# TSOC_PSoC4L.net
KiCad netlist of a schematic drawn in EAGLE
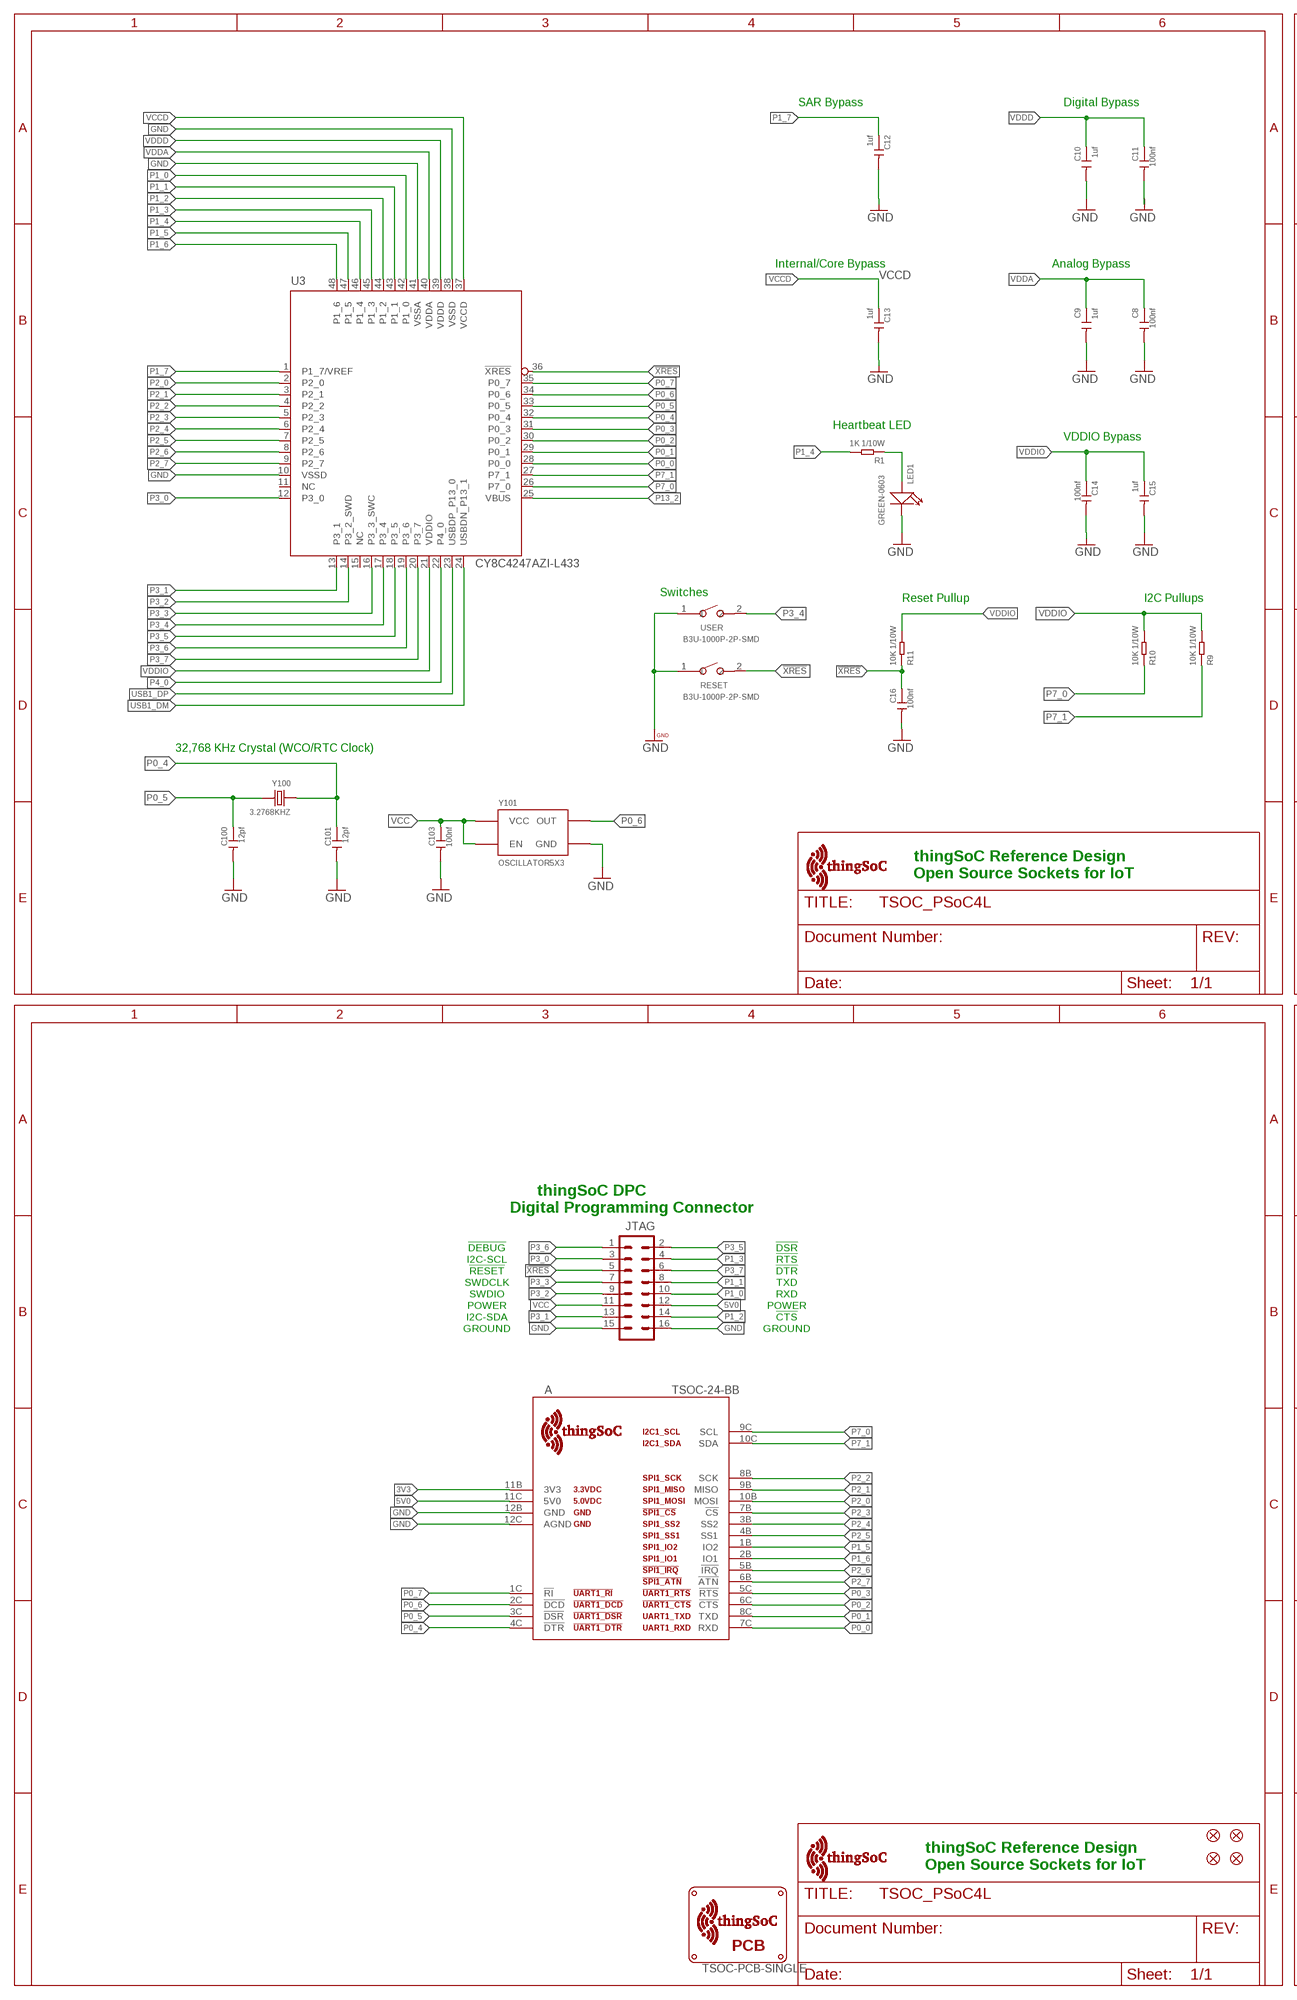
[diagram p0: schematic, sheet 1, part 1 of 2]
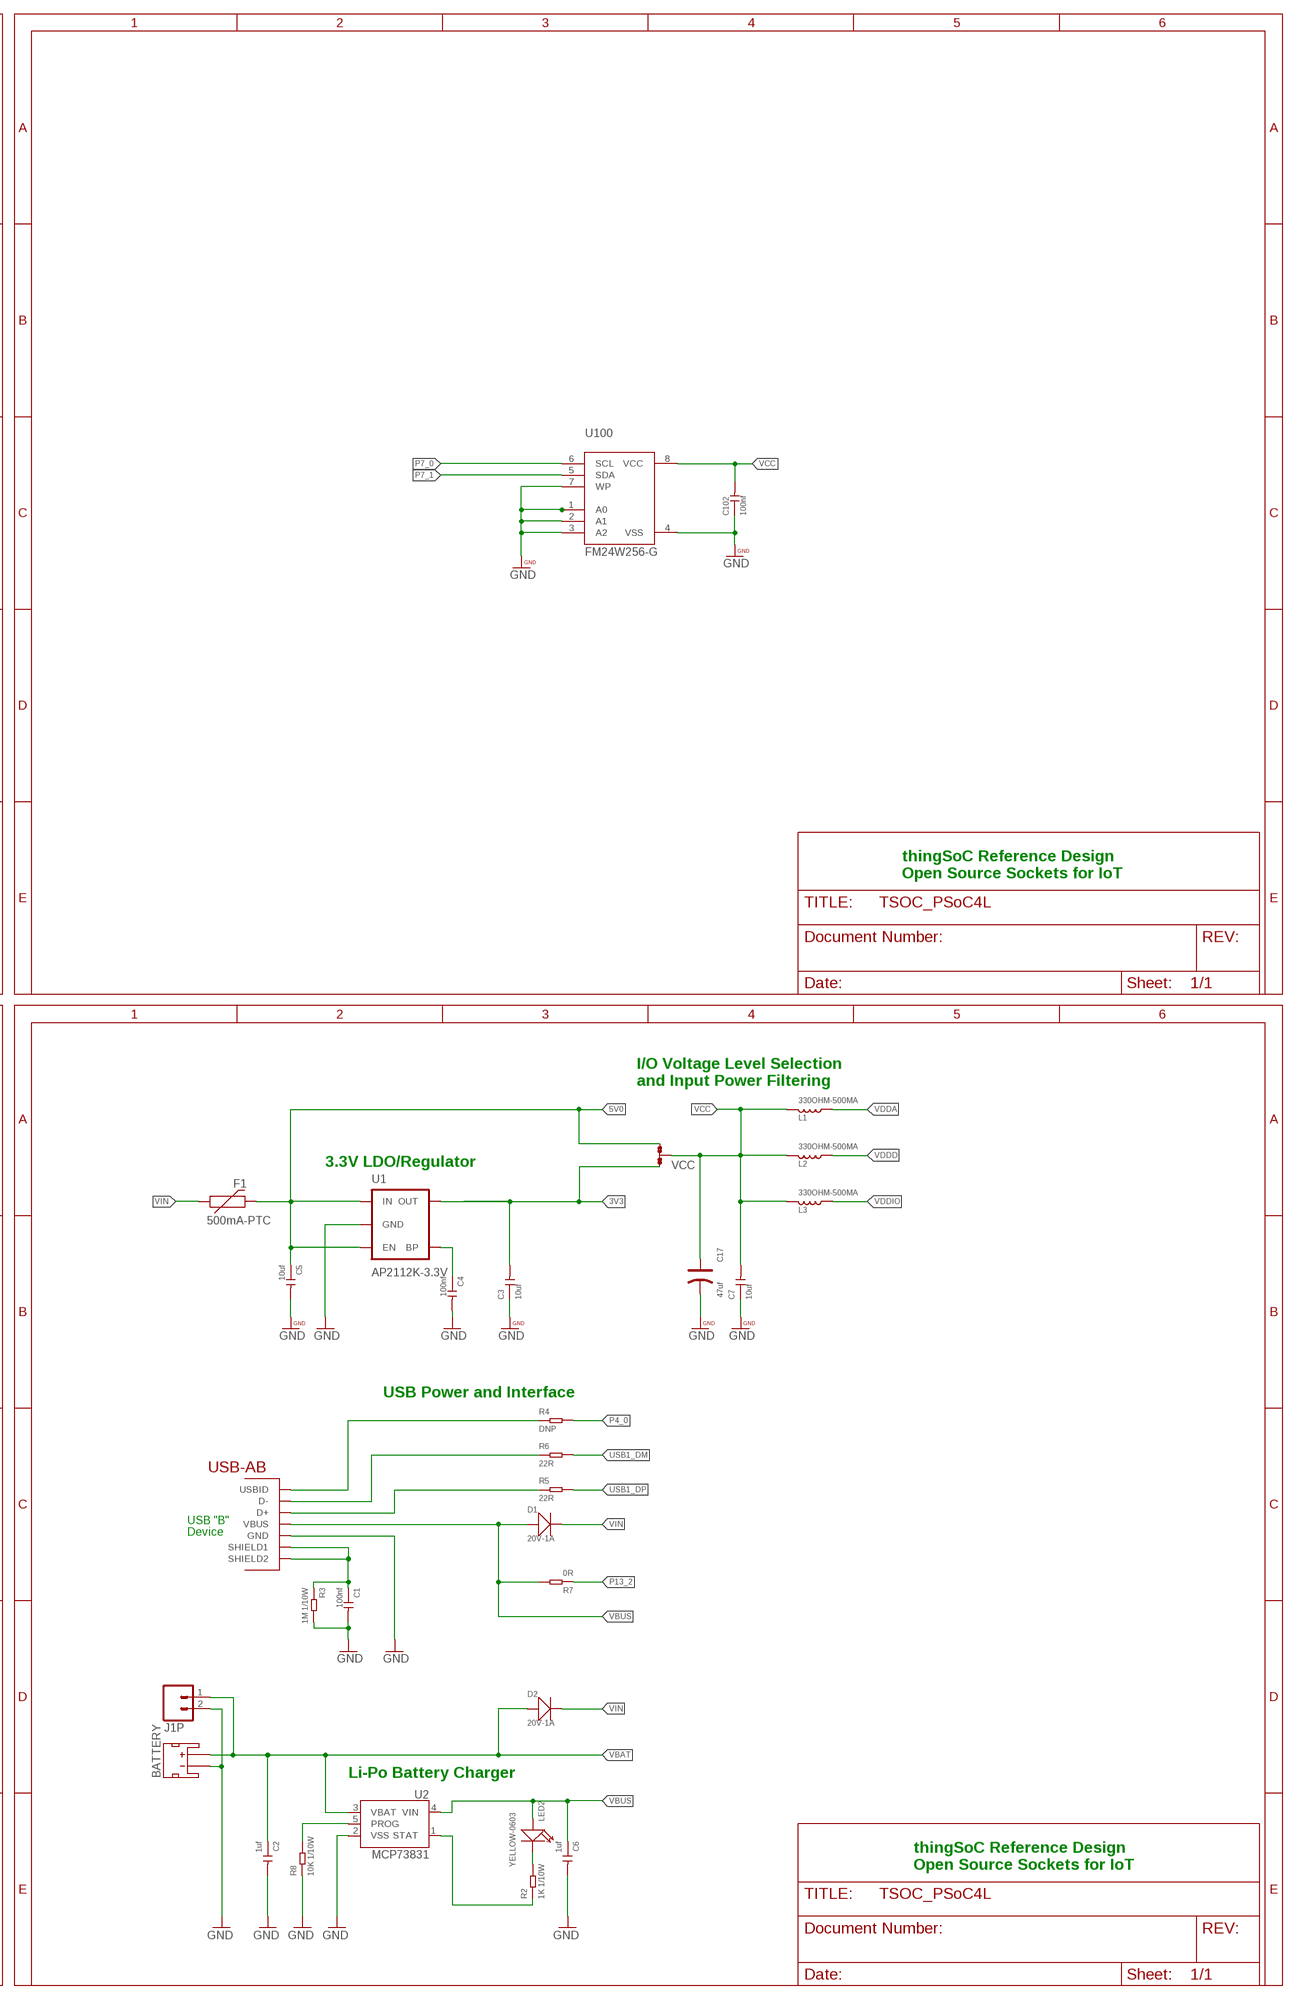
[diagram p1: schematic, sheet 1, part 2 of 2]

(export (version "E")
  (design (tool "Eeschema 10.0.6"))
  (components
    (comp (ref "A")
      (value "TSOC-24-BB")
      (footprint "eagle-import:TSOC-BB-S24")
      (libsource (lib "eagle-import") (part "TSOC-24-BB"))
    )
    (comp (ref "BATTERY")
      (value "JST_2MM_MALE")
      (footprint "eagle-import:JST-2-SMD")
      (libsource (lib "eagle-import") (part "JST_2MM_MALE"))
    )
    (comp (ref "C1")
      (value "100nf")
      (footprint "eagle-import:C0603")
      (fields (field (name "MPN") "CC0603KRX7R9BB104"))
      (libsource (lib "eagle-import") (part "CERAMIC-100NF-50V-10%-X7R(0603)"))
    )
    (comp (ref "C2")
      (value "1uf")
      (footprint "eagle-import:C0603")
      (fields (field (name "MPN") "CC0603KRX7R8BB105"))
      (libsource (lib "eagle-import") (part "CERAMIC-1UF-25V-10%-X7R(0603)"))
    )
    (comp (ref "C3")
      (value "10uf")
      (footprint "eagle-import:C0603")
      (fields (field (name "MPN") "CC0603KRX5R6BB106"))
      (libsource (lib "eagle-import") (part "CERAMIC-10UF-10V-10%-X5R(0603)"))
    )
    (comp (ref "C4")
      (value "100nf")
      (footprint "eagle-import:C0603")
      (fields (field (name "MPN") "CC0603KRX7R9BB104"))
      (libsource (lib "eagle-import") (part "CERAMIC-100NF-50V-10%-X7R(0603)"))
    )
    (comp (ref "C5")
      (value "10uf")
      (footprint "eagle-import:C0603")
      (fields (field (name "MPN") "CC0603KRX5R6BB106"))
      (libsource (lib "eagle-import") (part "CERAMIC-10UF-10V-10%-X5R(0603)"))
    )
    (comp (ref "C6")
      (value "1uf")
      (footprint "eagle-import:C0603")
      (fields (field (name "MPN") "CC0603KRX7R8BB105"))
      (libsource (lib "eagle-import") (part "CERAMIC-1UF-25V-10%-X7R(0603)"))
    )
    (comp (ref "C7")
      (value "10uf")
      (footprint "eagle-import:C0603")
      (fields (field (name "MPN") "CC0603KRX5R6BB106"))
      (libsource (lib "eagle-import") (part "CERAMIC-10UF-10V-10%-X5R(0603)"))
    )
    (comp (ref "C8")
      (value "100nf")
      (footprint "eagle-import:C0603")
      (fields (field (name "MPN") "CC0603KRX7R9BB104"))
      (libsource (lib "eagle-import") (part "CERAMIC-100NF-50V-10%-X7R(0603)"))
    )
    (comp (ref "C9")
      (value "1uf")
      (footprint "eagle-import:C0603")
      (fields (field (name "MPN") "CC0603KRX7R8BB105"))
      (libsource (lib "eagle-import") (part "CERAMIC-1UF-25V-10%-X7R(0603)"))
    )
    (comp (ref "C10")
      (value "1uf")
      (footprint "eagle-import:C0603")
      (fields (field (name "MPN") "CC0603KRX7R8BB105"))
      (libsource (lib "eagle-import") (part "CERAMIC-1UF-25V-10%-X7R(0603)"))
    )
    (comp (ref "C11")
      (value "100nf")
      (footprint "eagle-import:C0603")
      (fields (field (name "MPN") "CC0603KRX7R9BB104"))
      (libsource (lib "eagle-import") (part "CERAMIC-100NF-50V-10%-X7R(0603)"))
    )
    (comp (ref "C12")
      (value "1uf")
      (footprint "eagle-import:C0603")
      (fields (field (name "MPN") "CC0603KRX7R8BB105"))
      (libsource (lib "eagle-import") (part "CERAMIC-1UF-25V-10%-X7R(0603)"))
    )
    (comp (ref "C13")
      (value "1uf")
      (footprint "eagle-import:C0603")
      (fields (field (name "MPN") "CC0603KRX7R8BB105"))
      (libsource (lib "eagle-import") (part "CERAMIC-1UF-25V-10%-X7R(0603)"))
    )
    (comp (ref "C14")
      (value "100nf")
      (footprint "eagle-import:C0603")
      (fields (field (name "MPN") "CC0603KRX7R9BB104"))
      (libsource (lib "eagle-import") (part "CERAMIC-100NF-50V-10%-X7R(0603)"))
    )
    (comp (ref "C15")
      (value "1uf")
      (footprint "eagle-import:C0603")
      (fields (field (name "MPN") "CC0603KRX7R8BB105"))
      (libsource (lib "eagle-import") (part "CERAMIC-1UF-25V-10%-X7R(0603)"))
    )
    (comp (ref "C16")
      (value "100nf")
      (footprint "eagle-import:C0603")
      (fields (field (name "MPN") "CC0603KRX7R9BB104"))
      (libsource (lib "eagle-import") (part "CERAMIC-100NF-50V-10%-X7R(0603)"))
    )
    (comp (ref "C17")
      (value "47uf")
      (footprint "eagle-import:AVX-A")
      (fields (field (name "MPN") "TAJA476*006#NJ"))
      (libsource (lib "eagle-import") (part "TANTALUM-SMD-47UF-6.3V(AVX-A)"))
    )
    (comp (ref "C100")
      (value "12pf")
      (footprint "eagle-import:C0603")
      (fields (field (name "MPN") "CC0603JRNPO9BN120"))
      (libsource (lib "eagle-import") (part "CERAMIC-12PF-50V-5%-NPO(0603)"))
    )
    (comp (ref "C101")
      (value "12pf")
      (footprint "eagle-import:C0603")
      (fields (field (name "MPN") "CC0603JRNPO9BN120"))
      (libsource (lib "eagle-import") (part "CERAMIC-12PF-50V-5%-NPO(0603)"))
    )
    (comp (ref "C102")
      (value "100nf")
      (footprint "eagle-import:C0603")
      (fields (field (name "MPN") "CC0603KRX7R9BB104"))
      (libsource (lib "eagle-import") (part "CERAMIC-100NF-50V-10%-X7R(0603)"))
    )
    (comp (ref "C103")
      (value "100nf")
      (footprint "eagle-import:C0603")
      (fields (field (name "MPN") "CC0603KRX7R9BB104"))
      (libsource (lib "eagle-import") (part "CERAMIC-100NF-50V-10%-X7R(0603)"))
    )
    (comp (ref "D1")
      (value "20V-1A")
      (footprint "eagle-import:SOD-123")
      (fields (field (name "MPN") "B5819W"))
      (libsource (lib "eagle-import") (part "SMD-DIODE-SCHOTTKY-20V-1A(SOD-123)"))
    )
    (comp (ref "D2")
      (value "20V-1A")
      (footprint "eagle-import:SOD-123")
      (fields (field (name "MPN") "B5819W"))
      (libsource (lib "eagle-import") (part "SMD-DIODE-SCHOTTKY-20V-1A(SOD-123)"))
    )
    (comp (ref "F1")
      (value "500mA-PTC")
      (footprint "eagle-import:PTC-1206")
      (libsource (lib "eagle-import") (part "PTCSMD"))
    )
    (comp (ref "FID1")
      (value "FIDUCIALUFIDUCIAL")
      (footprint "eagle-import:MICRO-FIDUCIAL")
      (libsource (lib "eagle-import") (part "FIDUCIALUFIDUCIAL"))
    )
    (comp (ref "FID2")
      (value "FIDUCIALUFIDUCIAL")
      (footprint "eagle-import:MICRO-FIDUCIAL")
      (libsource (lib "eagle-import") (part "FIDUCIALUFIDUCIAL"))
    )
    (comp (ref "FID3")
      (value "FIDUCIALUFIDUCIAL")
      (footprint "eagle-import:MICRO-FIDUCIAL")
      (libsource (lib "eagle-import") (part "FIDUCIALUFIDUCIAL"))
    )
    (comp (ref "FID4")
      (value "FIDUCIALUFIDUCIAL")
      (footprint "eagle-import:MICRO-FIDUCIAL")
      (libsource (lib "eagle-import") (part "FIDUCIALUFIDUCIAL"))
    )
    (comp (ref "J1P")
      (value "M02-JST-2-PTH-NO_SILK")
      (footprint "eagle-import:JST-2-PTH-NS")
      (libsource (lib "eagle-import") (part "M02-JST-2-PTH-NO_SILK"))
    )
    (comp (ref "JTAG")
      (value "M08X2")
      (footprint "eagle-import:2X8")
      (libsource (lib "eagle-import") (part "M08X2"))
    )
    (comp (ref "L1")
      (value "330OHM-500MA")
      (footprint "eagle-import:L0603")
      (fields (field (name "MPN") "BLM18AG121SN1D"))
      (libsource (lib "eagle-import") (part "SMD-FERRITE-CHIP-120-OHM-500MA(0603)"))
    )
    (comp (ref "L2")
      (value "330OHM-500MA")
      (footprint "eagle-import:L0603")
      (fields (field (name "MPN") "BLM18AG121SN1D"))
      (libsource (lib "eagle-import") (part "SMD-FERRITE-CHIP-120-OHM-500MA(0603)"))
    )
    (comp (ref "L3")
      (value "330OHM-500MA")
      (footprint "eagle-import:L0603")
      (fields (field (name "MPN") "BLM18AG121SN1D"))
      (libsource (lib "eagle-import") (part "SMD-FERRITE-CHIP-120-OHM-500MA(0603)"))
    )
    (comp (ref "LED1")
      (value "GREEN-0603")
      (footprint "eagle-import:LED-0603")
      (fields (field (name "MPN") "19-217-G7C-AN1P2-3T"))
      (libsource (lib "eagle-import") (part "SMD-LED-CLEAR-GREEN(0603)"))
    )
    (comp (ref "LED2")
      (value "YELLOW-0603")
      (footprint "eagle-import:LED-0603")
      (fields (field (name "MPN") "19-217-Y5C-AM1N1VY-3T"))
      (libsource (lib "eagle-import") (part "SMD-LED-CLEAR-YELLOW(0603)"))
    )
    (comp (ref "R1")
      (value "1K 1/10W")
      (footprint "eagle-import:R0603")
      (fields (field (name "MPN") "RC0603JR-071KL"))
      (libsource (lib "eagle-import") (part "SMD-RES-1K-5%-1/10W(0603)"))
    )
    (comp (ref "R2")
      (value "1K 1/10W")
      (footprint "eagle-import:R0603")
      (fields (field (name "MPN") "RC0603JR-071KL"))
      (libsource (lib "eagle-import") (part "SMD-RES-1K-5%-1/10W(0603)"))
    )
    (comp (ref "R3")
      (value "1M 1/10W")
      (footprint "eagle-import:R0603")
      (fields (field (name "MPN") "RC0603JR-071ML"))
      (libsource (lib "eagle-import") (part "SMD-RES-1M-5%-1/10W(0603)"))
    )
    (comp (ref "R4")
      (value "DNP")
      (footprint "eagle-import:R0603")
      (fields (field (name "MPN") "RC0603JR-0722RL"))
      (libsource (lib "eagle-import") (part "SMD-RES-22R-5%-1/10W(0603)"))
    )
    (comp (ref "R5")
      (value "22R")
      (footprint "eagle-import:R0603")
      (fields (field (name "MPN") "RC0603JR-0722RL"))
      (libsource (lib "eagle-import") (part "SMD-RES-22R-5%-1/10W(0603)"))
    )
    (comp (ref "R6")
      (value "22R")
      (footprint "eagle-import:R0603")
      (fields (field (name "MPN") "RC0603JR-0722RL"))
      (libsource (lib "eagle-import") (part "SMD-RES-22R-5%-1/10W(0603)"))
    )
    (comp (ref "R7")
      (value "0R")
      (footprint "eagle-import:R0603")
      (fields (field (name "MPN") "RC0603JR-070RL"))
      (libsource (lib "eagle-import") (part "SMD-RES-0R-5%-1/10W(0603)"))
    )
    (comp (ref "R8")
      (value "10K 1/10W")
      (footprint "eagle-import:R0603")
      (fields (field (name "MPN") "RC0603JR-0710KL"))
      (libsource (lib "eagle-import") (part "SMD-RES-10K-5%-1/10W(0603)"))
    )
    (comp (ref "R9")
      (value "10K 1/10W")
      (footprint "eagle-import:R0603")
      (fields (field (name "MPN") "RC0603JR-0710KL"))
      (libsource (lib "eagle-import") (part "SMD-RES-10K-5%-1/10W(0603)"))
    )
    (comp (ref "R10")
      (value "10K 1/10W")
      (footprint "eagle-import:R0603")
      (fields (field (name "MPN") "RC0603JR-0710KL"))
      (libsource (lib "eagle-import") (part "SMD-RES-10K-5%-1/10W(0603)"))
    )
    (comp (ref "R11")
      (value "10K 1/10W")
      (footprint "eagle-import:R0603")
      (fields (field (name "MPN") "RC0603JR-0710KL"))
      (libsource (lib "eagle-import") (part "SMD-RES-10K-5%-1/10W(0603)"))
    )
    (comp (ref "RESET")
      (value "B3U-1000P-2P-SMD")
      (footprint "eagle-import:SW2-2.6-3.0X2.5X1.2+0.4MM")
      (libsource (lib "eagle-import") (part "SMD-BUTTON(2P-3.0X2.5X1.2+0.4MM)-B3U-1000P-2P-SMD"))
    )
    (comp (ref "U$1")
      (value "TSOC-PCB-SINGLE")
      (footprint "eagle-import:TSOC-BB-BRD-DIM")
      (libsource (lib "eagle-import") (part "TSOC-PCB-SINGLE"))
    )
    (comp (ref "U$100")
      (value "TSOC-LOGO-LRG")
      (footprint "eagle-import:TSOC-LOGO-LRG")
      (libsource (lib "eagle-import") (part "TSOC-LOGO-LRG"))
    )
    (comp (ref "U$101")
      (value "TSOC-LOGO-SMALL")
      (footprint "eagle-import:TSOC-LOGO-SML")
      (libsource (lib "eagle-import") (part "TSOC-LOGO-SMALL"))
    )
    (comp (ref "U1")
      (value "AP2112K-3.3V")
      (footprint "eagle-import:SOT23-5")
      (libsource (lib "eagle-import") (part "V_REG_LDOSMD"))
    )
    (comp (ref "U2")
      (value "MCP73831")
      (footprint "eagle-import:SOT23-5")
      (libsource (lib "eagle-import") (part "MCP73831"))
    )
    (comp (ref "U3")
      (value "CY8C4247AZI-L433")
      (footprint "eagle-import:TQFP-7X7-48")
      (libsource (lib "eagle-import") (part "CY8C4247AZI-L433"))
    )
    (comp (ref "U100")
      (value "FM24W256-G")
      (footprint "eagle-import:SO08")
      (libsource (lib "eagle-import") (part "FM24W256-G"))
    )
    (comp (ref "USB")
      (value "USB_AB")
      (footprint "eagle-import:USB-AB-MICRO-SMD")
      (libsource (lib "eagle-import") (part "USB_AB"))
    )
    (comp (ref "USER")
      (value "B3U-1000P-2P-SMD")
      (footprint "eagle-import:SW2-2.6-3.0X2.5X1.2+0.4MM")
      (libsource (lib "eagle-import") (part "SMD-BUTTON(2P-3.0X2.5X1.2+0.4MM)-B3U-1000P-2P-SMD"))
    )
    (comp (ref "VCC")
      (value "JMP-3-1_2")
      (footprint "eagle-import:JMP-3-1_2")
      (libsource (lib "eagle-import") (part "JMP-3-1_2"))
    )
    (comp (ref "Y100")
      (value "3.2768KHZ")
      (footprint "eagle-import:X2-SMD-L2.0X1.2X0.55MM")
      (fields (field (name "MPN") "FC-12M"))
      (libsource (lib "eagle-import") (part "SMD-CRYSTAL-32.768KHZ-12.5PF-20PPM-90K(2P-L2.0X1.2MM)"))
    )
    (comp (ref "Y101")
      (value "OSCILLATOR5X3")
      (footprint "eagle-import:CRYSTAL-SMD-5X3")
      (libsource (lib "eagle-import") (part "OSCILLATOR5X3"))
    )
  )
  (nets
    (net (code "1") (name "/~{XRES}") (class "Default")
      (node (ref "C16") (pin "1") (pinfunction "1_1") (pintype "passive"))
      (node (ref "JTAG") (pin "5") (pinfunction "5_5") (pintype "passive"))
      (node (ref "R11") (pin "1") (pinfunction "1_1") (pintype "passive"))
      (node (ref "RESET") (pin "2") (pinfunction "2_2") (pintype "bidirectional"))
      (node (ref "U3") (pin "36") (pinfunction "~{XRES}_36") (pintype "bidirectional"))
    )
    (net (code "2") (name "3V3") (class "Default")
      (node (ref "A") (pin "11B") (pinfunction "3V3_11B") (pintype "bidirectional"))
      (node (ref "C3") (pin "2") (pinfunction "2_2") (pintype "passive"))
      (node (ref "U1") (pin "5") (pinfunction "OUT_5") (pintype "passive"))
      (node (ref "VCC") (pin "1") (pinfunction "1_1") (pintype "passive"))
    )
    (net (code "3") (name "5V0") (class "Default")
      (node (ref "A") (pin "11C") (pinfunction "5V0_11C") (pintype "bidirectional"))
      (node (ref "C5") (pin "1") (pinfunction "1_1") (pintype "passive"))
      (node (ref "F1") (pin "2") (pinfunction "2_2") (pintype "bidirectional"))
      (node (ref "JTAG") (pin "12") (pinfunction "12_12") (pintype "passive"))
      (node (ref "U1") (pin "1") (pinfunction "IN_1") (pintype "input"))
      (node (ref "U1") (pin "3") (pinfunction "EN_3") (pintype "input"))
      (node (ref "VCC") (pin "3") (pinfunction "3_3") (pintype "passive"))
    )
    (net (code "4") (name "GND") (class "Default")
      (node (ref "A") (pin "12B") (pinfunction "GND_12B") (pintype "bidirectional"))
      (node (ref "A") (pin "12C") (pinfunction "AGND_12C") (pintype "bidirectional"))
      (node (ref "BATTERY") (pin "1") (pinfunction "-_1") (pintype "bidirectional"))
      (node (ref "C1") (pin "2") (pinfunction "2_2") (pintype "passive"))
      (node (ref "C10") (pin "2") (pinfunction "2_2") (pintype "passive"))
      (node (ref "C100") (pin "2") (pinfunction "2_2") (pintype "passive"))
      (node (ref "C101") (pin "2") (pinfunction "2_2") (pintype "passive"))
      (node (ref "C102") (pin "1") (pinfunction "1_1") (pintype "passive"))
      (node (ref "C103") (pin "2") (pinfunction "2_2") (pintype "passive"))
      (node (ref "C11") (pin "2") (pinfunction "2_2") (pintype "passive"))
      (node (ref "C12") (pin "2") (pinfunction "2_2") (pintype "passive"))
      (node (ref "C13") (pin "2") (pinfunction "2_2") (pintype "passive"))
      (node (ref "C14") (pin "2") (pinfunction "2_2") (pintype "passive"))
      (node (ref "C15") (pin "2") (pinfunction "2_2") (pintype "passive"))
      (node (ref "C16") (pin "2") (pinfunction "2_2") (pintype "passive"))
      (node (ref "C17") (pin "-") (pinfunction "-_-") (pintype "passive"))
      (node (ref "C2") (pin "2") (pinfunction "2_2") (pintype "passive"))
      (node (ref "C3") (pin "1") (pinfunction "1_1") (pintype "passive"))
      (node (ref "C4") (pin "2") (pinfunction "2_2") (pintype "passive"))
      (node (ref "C5") (pin "2") (pinfunction "2_2") (pintype "passive"))
      (node (ref "C6") (pin "2") (pinfunction "2_2") (pintype "passive"))
      (node (ref "C7") (pin "1") (pinfunction "1_1") (pintype "passive"))
      (node (ref "C8") (pin "2") (pinfunction "2_2") (pintype "passive"))
      (node (ref "C9") (pin "2") (pinfunction "2_2") (pintype "passive"))
      (node (ref "J1P") (pin "2") (pinfunction "2_2") (pintype "passive"))
      (node (ref "JTAG") (pin "15") (pinfunction "15_15") (pintype "passive"))
      (node (ref "JTAG") (pin "16") (pinfunction "16_16") (pintype "passive"))
      (node (ref "LED1") (pin "-") (pinfunction "-_-") (pintype "passive"))
      (node (ref "R3") (pin "2") (pinfunction "2_2") (pintype "passive"))
      (node (ref "R8") (pin "1") (pinfunction "1_1") (pintype "passive"))
      (node (ref "RESET") (pin "1") (pinfunction "1_1") (pintype "bidirectional"))
      (node (ref "U1") (pin "2") (pinfunction "GND_2") (pintype "input"))
      (node (ref "U100") (pin "1") (pinfunction "A0_1") (pintype "bidirectional"))
      (node (ref "U100") (pin "2") (pinfunction "A1_2") (pintype "bidirectional"))
      (node (ref "U100") (pin "3") (pinfunction "A2_3") (pintype "bidirectional"))
      (node (ref "U100") (pin "4") (pinfunction "VSS_4") (pintype "power_in"))
      (node (ref "U100") (pin "7") (pinfunction "WP_7") (pintype "bidirectional"))
      (node (ref "U2") (pin "2") (pinfunction "VSS_2") (pintype "power_in"))
      (node (ref "U3") (pin "10") (pinfunction "VSSD_10") (pintype "bidirectional"))
      (node (ref "U3") (pin "38") (pinfunction "VSSD_38") (pintype "bidirectional"))
      (node (ref "U3") (pin "41") (pinfunction "VSSA_41") (pintype "bidirectional"))
      (node (ref "USB") (pin "GND") (pinfunction "GND_GND") (pintype "bidirectional"))
      (node (ref "USER") (pin "1") (pinfunction "1_1") (pintype "bidirectional"))
      (node (ref "Y101") (pin "2") (pinfunction "GND_2") (pintype "bidirectional"))
    )
    (net (code "5") (name "Net-(C1-Pad1)") (class "Default")
      (node (ref "C1") (pin "1") (pinfunction "1_1") (pintype "passive"))
      (node (ref "R3") (pin "1") (pinfunction "1_1") (pintype "passive"))
      (node (ref "USB") (pin "SHIELD1") (pinfunction "SHIELD1_SHIELD1") (pintype "bidirectional"))
      (node (ref "USB") (pin "SHIELD2") (pinfunction "SHIELD2_SHIELD2") (pintype "bidirectional"))
    )
    (net (code "6") (name "Net-(LED1-Pad+)") (class "Default")
      (node (ref "LED1") (pin "+") (pinfunction "+_+") (pintype "passive"))
      (node (ref "R1") (pin "1") (pinfunction "1_1") (pintype "passive"))
    )
    (net (code "7") (name "Net-(LED2-Pad-)") (class "Default")
      (node (ref "LED2") (pin "-") (pinfunction "-_-") (pintype "passive"))
      (node (ref "R2") (pin "2") (pinfunction "2_2") (pintype "passive"))
    )
    (net (code "8") (name "Net-(R5-Pad1)") (class "Default")
      (node (ref "R5") (pin "1") (pinfunction "1_1") (pintype "passive"))
      (node (ref "USB") (pin "D+") (pinfunction "D+_D+") (pintype "bidirectional"))
    )
    (net (code "9") (name "Net-(R6-Pad1)") (class "Default")
      (node (ref "R6") (pin "1") (pinfunction "1_1") (pintype "passive"))
      (node (ref "USB") (pin "D-") (pinfunction "D-_D-") (pintype "bidirectional"))
    )
    (net (code "10") (name "Net-(U1-BP)") (class "Default")
      (node (ref "C4") (pin "1") (pinfunction "1_1") (pintype "passive"))
      (node (ref "U1") (pin "4") (pinfunction "BP_4") (pintype "input"))
    )
    (net (code "11") (name "Net-(U2-PROG)") (class "Default")
      (node (ref "R8") (pin "2") (pinfunction "2_2") (pintype "passive"))
      (node (ref "U2") (pin "5") (pinfunction "PROG_5") (pintype "input"))
    )
    (net (code "12") (name "Net-(U2-STAT)") (class "Default")
      (node (ref "R2") (pin "1") (pinfunction "1_1") (pintype "passive"))
      (node (ref "U2") (pin "1") (pinfunction "STAT_1") (pintype "output"))
    )
    (net (code "13") (name "Net-(USB-USBID)") (class "Default")
      (node (ref "R4") (pin "1") (pinfunction "1_1") (pintype "passive"))
      (node (ref "USB") (pin "ID") (pinfunction "USBID_ID") (pintype "bidirectional"))
    )
    (net (code "14") (name "P0_0") (class "Default")
      (node (ref "A") (pin "7C") (pinfunction "RXD_7C") (pintype "bidirectional"))
      (node (ref "U3") (pin "28") (pinfunction "P0_0_28") (pintype "bidirectional"))
    )
    (net (code "15") (name "P0_1") (class "Default")
      (node (ref "A") (pin "8C") (pinfunction "TXD_8C") (pintype "bidirectional"))
      (node (ref "U3") (pin "29") (pinfunction "P0_1_29") (pintype "bidirectional"))
    )
    (net (code "16") (name "P0_2") (class "Default")
      (node (ref "A") (pin "6C") (pinfunction "~{CTS}_6C") (pintype "bidirectional"))
      (node (ref "U3") (pin "30") (pinfunction "P0_2_30") (pintype "input"))
    )
    (net (code "17") (name "P0_3") (class "Default")
      (node (ref "A") (pin "5C") (pinfunction "~{RTS}_5C") (pintype "bidirectional"))
      (node (ref "U3") (pin "31") (pinfunction "P0_3_31") (pintype "bidirectional"))
    )
    (net (code "18") (name "P0_4") (class "Default")
      (node (ref "A") (pin "4C") (pinfunction "~{DTR}_4C") (pintype "bidirectional"))
      (node (ref "C101") (pin "1") (pinfunction "1_1") (pintype "passive"))
      (node (ref "U3") (pin "32") (pinfunction "P0_4_32") (pintype "bidirectional"))
      (node (ref "Y100") (pin "1") (pinfunction "1_1") (pintype "passive"))
    )
    (net (code "19") (name "P0_5") (class "Default")
      (node (ref "A") (pin "3C") (pinfunction "~{DSR}_3C") (pintype "bidirectional"))
      (node (ref "C100") (pin "1") (pinfunction "1_1") (pintype "passive"))
      (node (ref "U3") (pin "33") (pinfunction "P0_5_33") (pintype "bidirectional"))
      (node (ref "Y100") (pin "2") (pinfunction "2_2") (pintype "passive"))
    )
    (net (code "20") (name "P0_6") (class "Default")
      (node (ref "A") (pin "2C") (pinfunction "~{DCD}_2C") (pintype "bidirectional"))
      (node (ref "U3") (pin "34") (pinfunction "P0_6_34") (pintype "power_in"))
      (node (ref "Y101") (pin "3") (pinfunction "OUT_3") (pintype "bidirectional"))
    )
    (net (code "21") (name "P0_7") (class "Default")
      (node (ref "A") (pin "1C") (pinfunction "~{RI}_1C") (pintype "bidirectional"))
      (node (ref "U3") (pin "35") (pinfunction "P0_7_35") (pintype "bidirectional"))
    )
    (net (code "22") (name "P1_0") (class "Default")
      (node (ref "JTAG") (pin "10") (pinfunction "10_10") (pintype "passive"))
      (node (ref "U3") (pin "42") (pinfunction "P1_0_42") (pintype "bidirectional"))
    )
    (net (code "23") (name "P1_1") (class "Default")
      (node (ref "JTAG") (pin "8") (pinfunction "8_8") (pintype "passive"))
      (node (ref "U3") (pin "43") (pinfunction "P1_1_43") (pintype "bidirectional"))
    )
    (net (code "24") (name "P1_2") (class "Default")
      (node (ref "JTAG") (pin "14") (pinfunction "14_14") (pintype "passive"))
      (node (ref "U3") (pin "44") (pinfunction "P1_2_44") (pintype "power_in"))
    )
    (net (code "25") (name "P1_3") (class "Default")
      (node (ref "JTAG") (pin "4") (pinfunction "4_4") (pintype "passive"))
      (node (ref "U3") (pin "45") (pinfunction "P1_3_45") (pintype "bidirectional"))
    )
    (net (code "26") (name "P1_4") (class "Default")
      (node (ref "R1") (pin "2") (pinfunction "2_2") (pintype "passive"))
      (node (ref "U3") (pin "46") (pinfunction "P1_4_46") (pintype "bidirectional"))
    )
    (net (code "27") (name "P1_5") (class "Default")
      (node (ref "A") (pin "1B") (pinfunction "IO2_1B") (pintype "bidirectional"))
      (node (ref "U3") (pin "47") (pinfunction "P1_5_47") (pintype "bidirectional"))
    )
    (net (code "28") (name "P1_6") (class "Default")
      (node (ref "A") (pin "2B") (pinfunction "IO1_2B") (pintype "bidirectional"))
      (node (ref "U3") (pin "48") (pinfunction "P1_6_48") (pintype "bidirectional"))
    )
    (net (code "29") (name "P1_7") (class "Default")
      (node (ref "C12") (pin "1") (pinfunction "1_1") (pintype "passive"))
      (node (ref "U3") (pin "1") (pinfunction "P1_7/VREF_1") (pintype "bidirectional"))
    )
    (net (code "30") (name "P2_0") (class "Default")
      (node (ref "A") (pin "10B") (pinfunction "MOSI_10B") (pintype "bidirectional"))
      (node (ref "U3") (pin "2") (pinfunction "P2_0_2") (pintype "bidirectional"))
    )
    (net (code "31") (name "P2_1") (class "Default")
      (node (ref "A") (pin "9B") (pinfunction "MISO_9B") (pintype "bidirectional"))
      (node (ref "U3") (pin "3") (pinfunction "P2_1_3") (pintype "bidirectional"))
    )
    (net (code "32") (name "P2_2") (class "Default")
      (node (ref "A") (pin "8B") (pinfunction "SCK_8B") (pintype "bidirectional"))
      (node (ref "U3") (pin "4") (pinfunction "P2_2_4") (pintype "power_in"))
    )
    (net (code "33") (name "P2_3") (class "Default")
      (node (ref "A") (pin "7B") (pinfunction "~{CS}_7B") (pintype "bidirectional"))
      (node (ref "U3") (pin "5") (pinfunction "P2_3_5") (pintype "bidirectional"))
    )
    (net (code "34") (name "P2_4") (class "Default")
      (node (ref "A") (pin "3B") (pinfunction "SS2_3B") (pintype "bidirectional"))
      (node (ref "U3") (pin "6") (pinfunction "P2_4_6") (pintype "bidirectional"))
    )
    (net (code "35") (name "P2_5") (class "Default")
      (node (ref "A") (pin "4B") (pinfunction "SS1_4B") (pintype "bidirectional"))
      (node (ref "U3") (pin "7") (pinfunction "P2_5_7") (pintype "bidirectional"))
    )
    (net (code "36") (name "P2_6") (class "Default")
      (node (ref "A") (pin "5B") (pinfunction "~{IRQ}_5B") (pintype "bidirectional"))
      (node (ref "U3") (pin "8") (pinfunction "P2_6_8") (pintype "power_in"))
    )
    (net (code "37") (name "P2_7") (class "Default")
      (node (ref "A") (pin "6B") (pinfunction "~{ATN}_6B") (pintype "bidirectional"))
      (node (ref "U3") (pin "9") (pinfunction "P2_7_9") (pintype "bidirectional"))
    )
    (net (code "38") (name "P3_0") (class "Default")
      (node (ref "JTAG") (pin "3") (pinfunction "3_3") (pintype "passive"))
      (node (ref "U3") (pin "12") (pinfunction "P3_0_12") (pintype "bidirectional"))
    )
    (net (code "39") (name "P3_1") (class "Default")
      (node (ref "JTAG") (pin "13") (pinfunction "13_13") (pintype "passive"))
      (node (ref "U3") (pin "13") (pinfunction "P3_1_13") (pintype "bidirectional"))
    )
    (net (code "40") (name "P3_2") (class "Default")
      (node (ref "JTAG") (pin "9") (pinfunction "9_9") (pintype "passive"))
      (node (ref "U3") (pin "14") (pinfunction "P3_2_SWD_14") (pintype "bidirectional"))
    )
    (net (code "41") (name "P3_3") (class "Default")
      (node (ref "JTAG") (pin "7") (pinfunction "7_7") (pintype "passive"))
      (node (ref "U3") (pin "16") (pinfunction "P3_3_SWC_16") (pintype "bidirectional"))
    )
    (net (code "42") (name "P3_4") (class "Default")
      (node (ref "U3") (pin "17") (pinfunction "P3_4_17") (pintype "bidirectional"))
      (node (ref "USER") (pin "2") (pinfunction "2_2") (pintype "bidirectional"))
    )
    (net (code "43") (name "P3_5") (class "Default")
      (node (ref "JTAG") (pin "2") (pinfunction "2_2") (pintype "passive"))
      (node (ref "U3") (pin "18") (pinfunction "P3_5_18") (pintype "bidirectional"))
    )
    (net (code "44") (name "P3_6") (class "Default")
      (node (ref "JTAG") (pin "1") (pinfunction "1_1") (pintype "passive"))
      (node (ref "U3") (pin "19") (pinfunction "P3_6_19") (pintype "power_in"))
    )
    (net (code "45") (name "P3_7") (class "Default")
      (node (ref "JTAG") (pin "6") (pinfunction "6_6") (pintype "passive"))
      (node (ref "U3") (pin "20") (pinfunction "P3_7_20") (pintype "bidirectional"))
    )
    (net (code "46") (name "P4_0") (class "Default")
      (node (ref "R4") (pin "2") (pinfunction "2_2") (pintype "passive"))
      (node (ref "U3") (pin "22") (pinfunction "P4_0_22") (pintype "bidirectional"))
    )
    (net (code "47") (name "P7_0") (class "Default")
      (node (ref "A") (pin "9C") (pinfunction "SCL_9C") (pintype "bidirectional"))
      (node (ref "R10") (pin "1") (pinfunction "1_1") (pintype "passive"))
      (node (ref "U100") (pin "6") (pinfunction "SCL_6") (pintype "bidirectional"))
      (node (ref "U3") (pin "26") (pinfunction "P7_0_26") (pintype "bidirectional"))
    )
    (net (code "48") (name "P7_1") (class "Default")
      (node (ref "A") (pin "10C") (pinfunction "SDA_10C") (pintype "bidirectional"))
      (node (ref "R9") (pin "1") (pinfunction "1_1") (pintype "passive"))
      (node (ref "U100") (pin "5") (pinfunction "SDA_5") (pintype "bidirectional"))
      (node (ref "U3") (pin "27") (pinfunction "P7_1_27") (pintype "bidirectional"))
    )
    (net (code "49") (name "P13_2") (class "Default")
      (node (ref "R7") (pin "1") (pinfunction "1_1") (pintype "passive"))
      (node (ref "U3") (pin "25") (pinfunction "VBUS_25") (pintype "bidirectional"))
    )
    (net (code "50") (name "USB1_DM") (class "Default")
      (node (ref "R6") (pin "2") (pinfunction "2_2") (pintype "passive"))
      (node (ref "U3") (pin "24") (pinfunction "USBDN_P13_1_24") (pintype "bidirectional"))
    )
    (net (code "51") (name "USB1_DP") (class "Default")
      (node (ref "R5") (pin "2") (pinfunction "2_2") (pintype "passive"))
      (node (ref "U3") (pin "23") (pinfunction "USBDP_P13_0_23") (pintype "bidirectional"))
    )
    (net (code "52") (name "VBAT") (class "Default")
      (node (ref "BATTERY") (pin "2") (pinfunction "+_2") (pintype "bidirectional"))
      (node (ref "C2") (pin "1") (pinfunction "1_1") (pintype "passive"))
      (node (ref "D2") (pin "+") (pinfunction "+_+") (pintype "passive"))
      (node (ref "J1P") (pin "1") (pinfunction "1_1") (pintype "passive"))
      (node (ref "U2") (pin "3") (pinfunction "VBAT_3") (pintype "power_in"))
    )
    (net (code "53") (name "VBUS") (class "Default")
      (node (ref "C6") (pin "1") (pinfunction "1_1") (pintype "passive"))
      (node (ref "D1") (pin "+") (pinfunction "+_+") (pintype "passive"))
      (node (ref "LED2") (pin "+") (pinfunction "+_+") (pintype "passive"))
      (node (ref "R7") (pin "2") (pinfunction "2_2") (pintype "passive"))
      (node (ref "U2") (pin "4") (pinfunction "VIN_4") (pintype "power_in"))
      (node (ref "USB") (pin "VBUS") (pinfunction "VBUS_VBUS") (pintype "bidirectional"))
    )
    (net (code "54") (name "VCC") (class "Default")
      (node (ref "C102") (pin "2") (pinfunction "2_2") (pintype "passive"))
      (node (ref "C103") (pin "1") (pinfunction "1_1") (pintype "passive"))
      (node (ref "C17") (pin "+") (pinfunction "+_+") (pintype "passive"))
      (node (ref "C7") (pin "2") (pinfunction "2_2") (pintype "passive"))
      (node (ref "JTAG") (pin "11") (pinfunction "11_11") (pintype "passive"))
      (node (ref "L1") (pin "1") (pinfunction "1_1") (pintype "passive"))
      (node (ref "L2") (pin "1") (pinfunction "1_1") (pintype "passive"))
      (node (ref "L3") (pin "1") (pinfunction "1_1") (pintype "passive"))
      (node (ref "U100") (pin "8") (pinfunction "VCC_8") (pintype "power_in"))
      (node (ref "VCC") (pin "2") (pinfunction "2_2") (pintype "passive"))
      (node (ref "Y101") (pin "1") (pinfunction "EN_1") (pintype "bidirectional"))
      (node (ref "Y101") (pin "4") (pinfunction "VCC_4") (pintype "bidirectional"))
    )
    (net (code "55") (name "VCCD") (class "Default")
      (node (ref "C13") (pin "1") (pinfunction "1_1") (pintype "passive"))
      (node (ref "U3") (pin "37") (pinfunction "VCCD_37") (pintype "bidirectional"))
    )
    (net (code "56") (name "VDDA") (class "Default")
      (node (ref "C8") (pin "1") (pinfunction "1_1") (pintype "passive"))
      (node (ref "C9") (pin "1") (pinfunction "1_1") (pintype "passive"))
      (node (ref "L1") (pin "2") (pinfunction "2_2") (pintype "passive"))
      (node (ref "U3") (pin "40") (pinfunction "VDDA_40") (pintype "bidirectional"))
    )
    (net (code "57") (name "VDDD") (class "Default")
      (node (ref "C10") (pin "1") (pinfunction "1_1") (pintype "passive"))
      (node (ref "C11") (pin "1") (pinfunction "1_1") (pintype "passive"))
      (node (ref "L2") (pin "2") (pinfunction "2_2") (pintype "passive"))
      (node (ref "U3") (pin "39") (pinfunction "VDDD_39") (pintype "bidirectional"))
    )
    (net (code "58") (name "VDDIO") (class "Default")
      (node (ref "C14") (pin "1") (pinfunction "1_1") (pintype "passive"))
      (node (ref "C15") (pin "1") (pinfunction "1_1") (pintype "passive"))
      (node (ref "L3") (pin "2") (pinfunction "2_2") (pintype "passive"))
      (node (ref "R10") (pin "2") (pinfunction "2_2") (pintype "passive"))
      (node (ref "R11") (pin "2") (pinfunction "2_2") (pintype "passive"))
      (node (ref "R9") (pin "2") (pinfunction "2_2") (pintype "passive"))
      (node (ref "U3") (pin "21") (pinfunction "VDDIO_21") (pintype "bidirectional"))
    )
    (net (code "59") (name "VIN") (class "Default")
      (node (ref "D1") (pin "-") (pinfunction "-_-") (pintype "passive"))
      (node (ref "D2") (pin "-") (pinfunction "-_-") (pintype "passive"))
      (node (ref "F1") (pin "1") (pinfunction "1_1") (pintype "bidirectional"))
    )
    (net (code "60") (name "unconnected-(BATTERY-PAD1-PadNC1)") (class "Default")
      (node (ref "BATTERY") (pin "NC1") (pinfunction "PAD1_NC1") (pintype "bidirectional"))
    )
    (net (code "61") (name "unconnected-(BATTERY-PAD2-PadNC2)") (class "Default")
      (node (ref "BATTERY") (pin "NC2") (pinfunction "PAD2_NC2") (pintype "bidirectional"))
    )
    (net (code "62") (name "unconnected-(U3-NC-Pad11)") (class "Default")
      (node (ref "U3") (pin "11") (pinfunction "NC_11") (pintype "bidirectional"))
    )
    (net (code "63") (name "unconnected-(U3-NC-Pad15)") (class "Default")
      (node (ref "U3") (pin "15") (pinfunction "NC_15") (pintype "bidirectional"))
    )
  )
)
